# AJH_Wasp_1_0.net
KiCad netlist of a schematic drawn in EAGLE
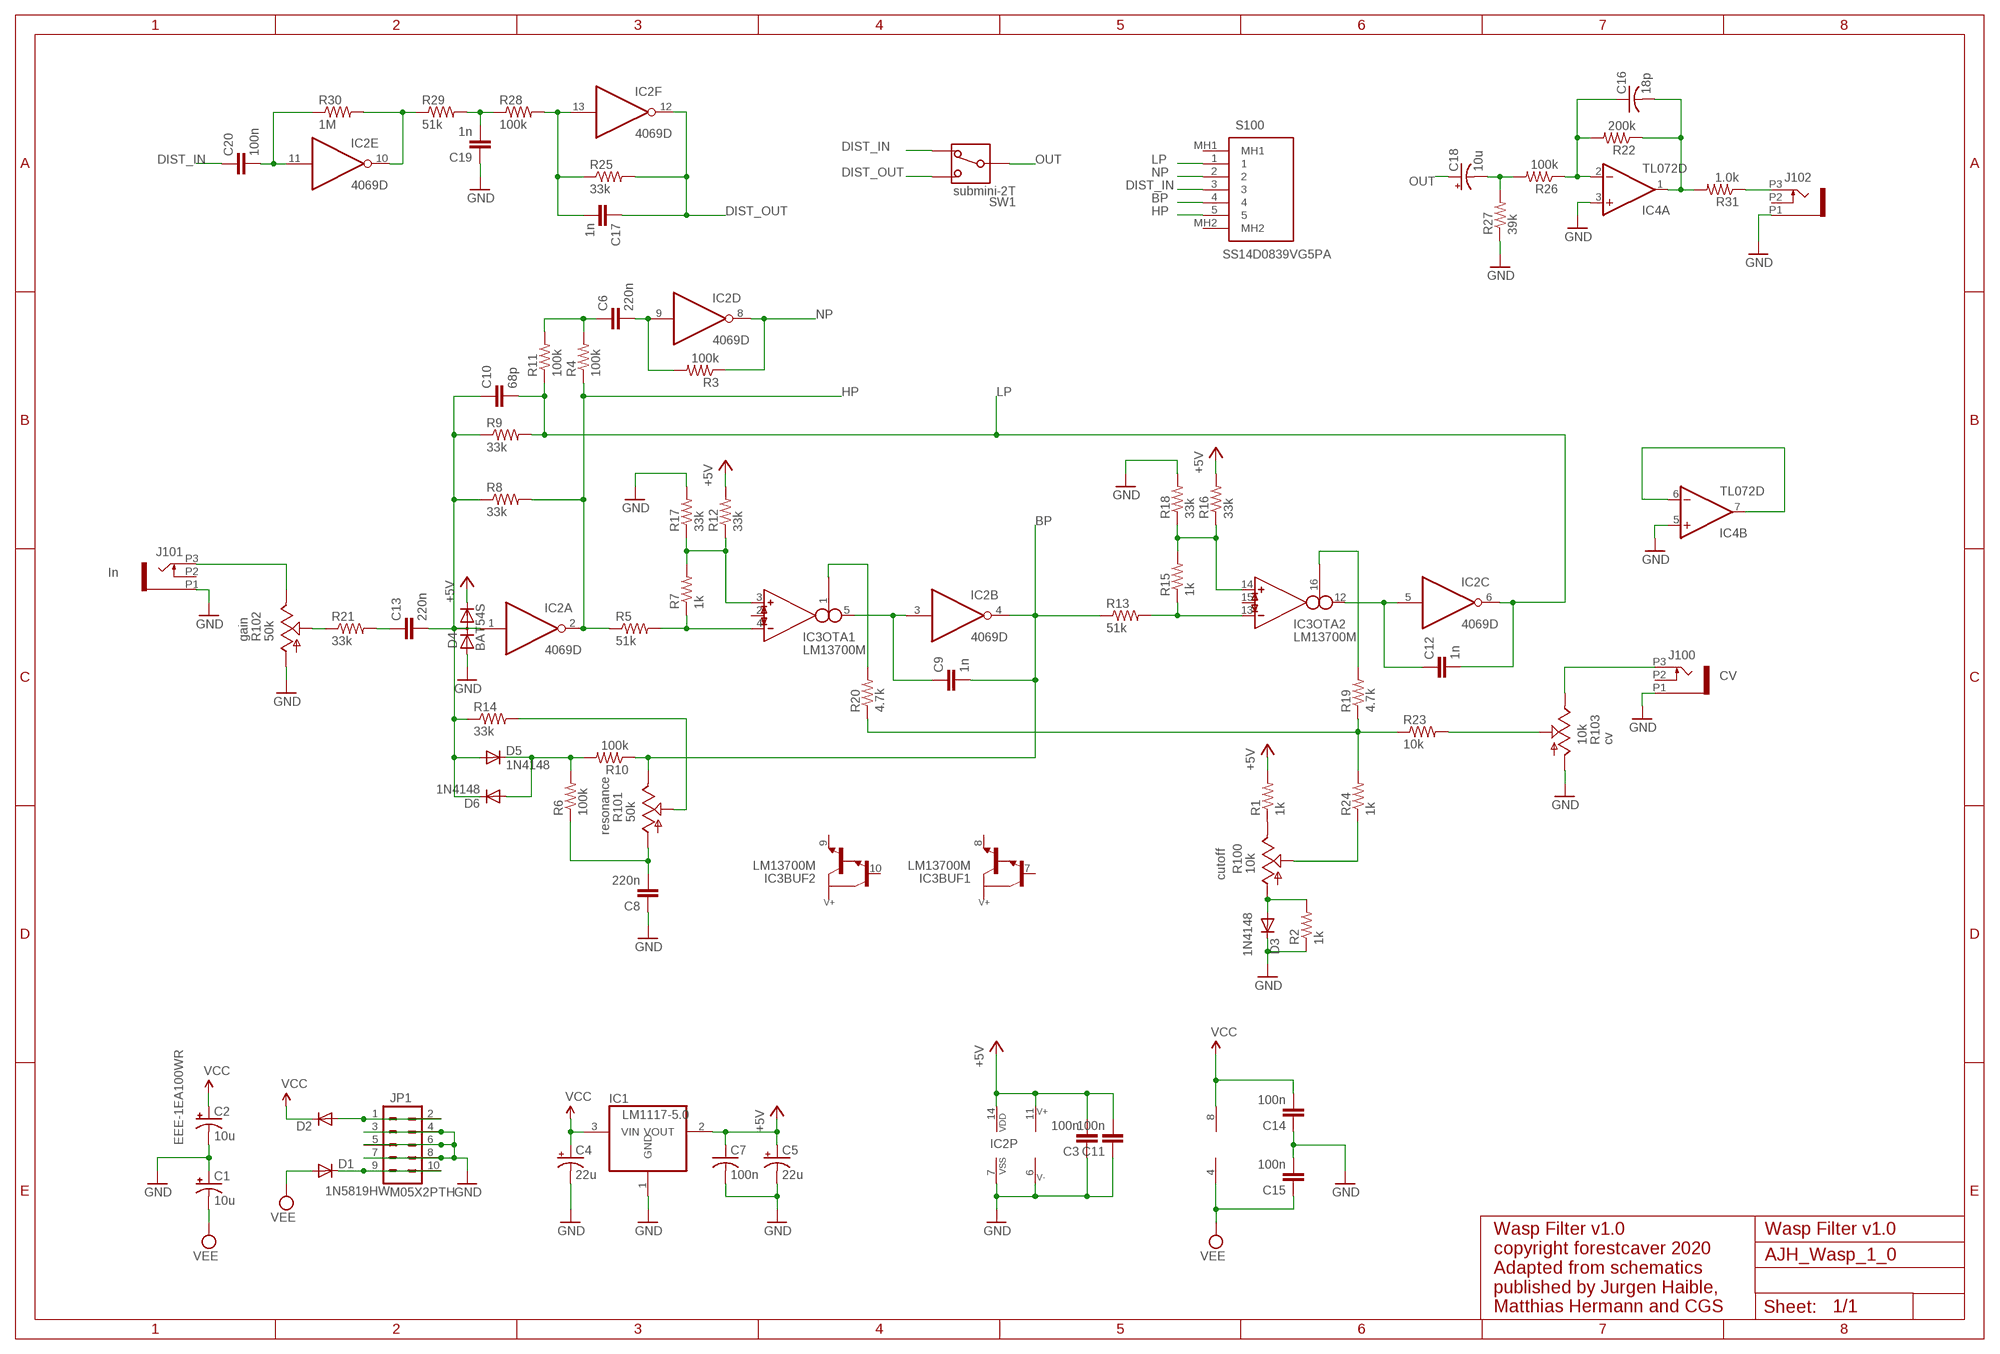
[diagram p0: schematic, sheet 1]

(export (version "E")
  (design (tool "Eeschema 10.0.6"))
  (components
    (comp (ref "C1")
      (value "10u")
      (footprint "eagle-import:PANASONIC_B")
      (libsource (lib "eagle-import") (part "CPOL-USB"))
    )
    (comp (ref "C2")
      (value "10u")
      (footprint "eagle-import:PANASONIC_B")
      (libsource (lib "eagle-import") (part "CPOL-USB"))
    )
    (comp (ref "C3")
      (value "100n")
      (footprint "eagle-import:C0603")
      (libsource (lib "eagle-import") (part "C-EUC0603"))
    )
    (comp (ref "C4")
      (value "22u")
      (footprint "eagle-import:PANASONIC_C")
      (libsource (lib "eagle-import") (part "CPOL-USC"))
    )
    (comp (ref "C5")
      (value "22u")
      (footprint "eagle-import:PANASONIC_C")
      (libsource (lib "eagle-import") (part "CPOL-USC"))
    )
    (comp (ref "C6")
      (value "220n")
      (footprint "eagle-import:C0603")
      (libsource (lib "eagle-import") (part "C-EUC0603"))
    )
    (comp (ref "C7")
      (value "100n")
      (footprint "eagle-import:C0603")
      (libsource (lib "eagle-import") (part "C-USC0603"))
    )
    (comp (ref "C8")
      (value "220n")
      (footprint "eagle-import:C0603")
      (libsource (lib "eagle-import") (part "C-EUC0603"))
    )
    (comp (ref "C9")
      (value "1n")
      (footprint "eagle-import:C0603")
      (libsource (lib "eagle-import") (part "C-EUC0603"))
    )
    (comp (ref "C10")
      (value "68p")
      (footprint "eagle-import:C0603")
      (libsource (lib "eagle-import") (part "C-EUC0603"))
    )
    (comp (ref "C11")
      (value "100n")
      (footprint "eagle-import:C0603")
      (libsource (lib "eagle-import") (part "C-EUC0603"))
    )
    (comp (ref "C12")
      (value "1n")
      (footprint "eagle-import:C0603")
      (libsource (lib "eagle-import") (part "C-EUC0603"))
    )
    (comp (ref "C13")
      (value "220n")
      (footprint "eagle-import:C0603")
      (libsource (lib "eagle-import") (part "C-EUC0603"))
    )
    (comp (ref "C14")
      (value "100n")
      (footprint "eagle-import:C0603")
      (libsource (lib "eagle-import") (part "C-EUC0603"))
    )
    (comp (ref "C15")
      (value "100n")
      (footprint "eagle-import:C0603")
      (libsource (lib "eagle-import") (part "C-EUC0603"))
    )
    (comp (ref "C16")
      (value "18p")
      (footprint "eagle-import:C0603")
      (libsource (lib "eagle-import") (part "C-USC0603"))
    )
    (comp (ref "C17")
      (value "1n")
      (footprint "eagle-import:C0603")
      (libsource (lib "eagle-import") (part "C-EUC0603"))
    )
    (comp (ref "C18")
      (value "10u")
      (footprint "eagle-import:PANASONIC_B")
      (libsource (lib "eagle-import") (part "CPOL-USB"))
    )
    (comp (ref "C19")
      (value "1n")
      (footprint "eagle-import:C0603")
      (libsource (lib "eagle-import") (part "C-EUC0603"))
    )
    (comp (ref "C20")
      (value "100n")
      (footprint "eagle-import:C0603")
      (libsource (lib "eagle-import") (part "C-EUC0603"))
    )
    (comp (ref "D1")
      (value "1N5819HW")
      (footprint "eagle-import:SOD123")
      (libsource (lib "eagle-import") (part "DIODE-SOD123"))
    )
    (comp (ref "D2")
      (value "1N5819HW")
      (footprint "eagle-import:SOD123")
      (libsource (lib "eagle-import") (part "DIODE-SOD123"))
    )
    (comp (ref "D3")
      (value "1N4148")
      (footprint "eagle-import:SOD523")
      (libsource (lib "eagle-import") (part "DIODE-SOD523"))
    )
    (comp (ref "D4")
      (value "BAT54S")
      (footprint "eagle-import:SOT23")
      (libsource (lib "eagle-import") (part "DIODE_2CACA-SOT23"))
    )
    (comp (ref "D5")
      (value "1N4148")
      (footprint "eagle-import:SOD523")
      (libsource (lib "eagle-import") (part "DIODE-SOD523"))
    )
    (comp (ref "D6")
      (value "1N4148")
      (footprint "eagle-import:SOD523")
      (libsource (lib "eagle-import") (part "DIODE-SOD523"))
    )
    (comp (ref "IC1")
      (value "LM1117-5.0")
      (footprint "eagle-import:SOT223")
      (libsource (lib "eagle-import") (part "REG1117"))
    )
    (comp (ref "IC2")
      (value "4069D")
      (footprint "eagle-import:SO14")
      (libsource (lib "eagle-import") (part "4069D"))
    )
    (comp (ref "IC3")
      (value "LM13700M")
      (footprint "eagle-import:SO16")
      (libsource (lib "eagle-import") (part "LM13700M"))
    )
    (comp (ref "IC4")
      (value "TL072D")
      (footprint "eagle-import:SO08")
      (libsource (lib "eagle-import") (part "TL072D"))
    )
    (comp (ref "J100")
      (value "PJ301_THONKICONN8")
      (footprint "eagle-import:WQP_PJ_301M8")
      (fields (field (name "LABEL") "CV"))
      (libsource (lib "eagle-import") (part "PJ301_THONKICONN8"))
    )
    (comp (ref "J101")
      (value "PJ301_THONKICONN8")
      (footprint "eagle-import:WQP_PJ_301M8")
      (fields (field (name "LABEL") "In"))
      (libsource (lib "eagle-import") (part "PJ301_THONKICONN8"))
    )
    (comp (ref "J102")
      (value "PJ301_THONKICONN6")
      (footprint "eagle-import:WQP_PJ_301M6")
      (libsource (lib "eagle-import") (part "PJ301_THONKICONN6"))
    )
    (comp (ref "JP1")
      (value "M05X2PTH")
      (footprint "eagle-import:AVR_ICSP")
      (libsource (lib "eagle-import") (part "M05X2PTH"))
    )
    (comp (ref "R1")
      (value "1k")
      (footprint "eagle-import:R0603")
      (libsource (lib "eagle-import") (part "rcl_334_R-US_R0603"))
    )
    (comp (ref "R2")
      (value "1k")
      (footprint "eagle-import:R0603")
      (libsource (lib "eagle-import") (part "rcl_334_R-US_R0603"))
    )
    (comp (ref "R3")
      (value "100k")
      (footprint "eagle-import:R0603")
      (libsource (lib "eagle-import") (part "rcl_334_R-US_R0603"))
    )
    (comp (ref "R4")
      (value "100k")
      (footprint "eagle-import:R0603")
      (libsource (lib "eagle-import") (part "rcl_334_R-US_R0603"))
    )
    (comp (ref "R5")
      (value "51k")
      (footprint "eagle-import:R0603")
      (libsource (lib "eagle-import") (part "rcl_334_R-US_R0603"))
    )
    (comp (ref "R6")
      (value "100k")
      (footprint "eagle-import:R0603")
      (libsource (lib "eagle-import") (part "rcl_334_R-US_R0603"))
    )
    (comp (ref "R7")
      (value "1k")
      (footprint "eagle-import:R0603")
      (libsource (lib "eagle-import") (part "rcl_334_R-US_R0603"))
    )
    (comp (ref "R8")
      (value "33k")
      (footprint "eagle-import:R0603")
      (libsource (lib "eagle-import") (part "rcl_334_R-US_R0603"))
    )
    (comp (ref "R9")
      (value "33k")
      (footprint "eagle-import:R0603")
      (libsource (lib "eagle-import") (part "rcl_334_R-US_R0603"))
    )
    (comp (ref "R10")
      (value "100k")
      (footprint "eagle-import:R0603")
      (libsource (lib "eagle-import") (part "rcl_334_R-US_R0603"))
    )
    (comp (ref "R11")
      (value "100k")
      (footprint "eagle-import:R0603")
      (libsource (lib "eagle-import") (part "rcl_334_R-US_R0603"))
    )
    (comp (ref "R12")
      (value "33k")
      (footprint "eagle-import:R0603")
      (libsource (lib "eagle-import") (part "rcl_334_R-US_R0603"))
    )
    (comp (ref "R13")
      (value "51k")
      (footprint "eagle-import:R0603")
      (libsource (lib "eagle-import") (part "rcl_334_R-US_R0603"))
    )
    (comp (ref "R14")
      (value "33k")
      (footprint "eagle-import:R0603")
      (libsource (lib "eagle-import") (part "rcl_334_R-US_R0603"))
    )
    (comp (ref "R15")
      (value "1k")
      (footprint "eagle-import:R0603")
      (libsource (lib "eagle-import") (part "rcl_334_R-US_R0603"))
    )
    (comp (ref "R16")
      (value "33k")
      (footprint "eagle-import:R0603")
      (libsource (lib "eagle-import") (part "rcl_334_R-US_R0603"))
    )
    (comp (ref "R17")
      (value "33k")
      (footprint "eagle-import:R0603")
      (libsource (lib "eagle-import") (part "rcl_334_R-US_R0603"))
    )
    (comp (ref "R18")
      (value "33k")
      (footprint "eagle-import:R0603")
      (libsource (lib "eagle-import") (part "rcl_334_R-US_R0603"))
    )
    (comp (ref "R19")
      (value "4.7k")
      (footprint "eagle-import:R0603")
      (libsource (lib "eagle-import") (part "rcl_334_R-US_R0603"))
    )
    (comp (ref "R20")
      (value "4.7k")
      (footprint "eagle-import:R0603")
      (libsource (lib "eagle-import") (part "rcl_334_R-US_R0603"))
    )
    (comp (ref "R21")
      (value "33k")
      (footprint "eagle-import:R0603")
      (libsource (lib "eagle-import") (part "rcl_334_R-US_R0603"))
    )
    (comp (ref "R22")
      (value "200k")
      (footprint "eagle-import:R0603")
      (libsource (lib "eagle-import") (part "R-US_R0603"))
    )
    (comp (ref "R23")
      (value "10k")
      (footprint "eagle-import:R0603")
      (libsource (lib "eagle-import") (part "rcl_334_R-US_R0603"))
    )
    (comp (ref "R24")
      (value "1k")
      (footprint "eagle-import:R0603")
      (libsource (lib "eagle-import") (part "rcl_334_R-US_R0603"))
    )
    (comp (ref "R25")
      (value "33k")
      (footprint "eagle-import:R0603")
      (libsource (lib "eagle-import") (part "rcl_334_R-US_R0603"))
    )
    (comp (ref "R26")
      (value "100k")
      (footprint "eagle-import:R0603")
      (libsource (lib "eagle-import") (part "R-US_R0603"))
    )
    (comp (ref "R27")
      (value "39k")
      (footprint "eagle-import:R0603")
      (libsource (lib "eagle-import") (part "R-US_R0603"))
    )
    (comp (ref "R28")
      (value "100k")
      (footprint "eagle-import:R0603")
      (libsource (lib "eagle-import") (part "rcl_334_R-US_R0603"))
    )
    (comp (ref "R29")
      (value "51k")
      (footprint "eagle-import:R0603")
      (libsource (lib "eagle-import") (part "rcl_334_R-US_R0603"))
    )
    (comp (ref "R30")
      (value "1M")
      (footprint "eagle-import:R0603")
      (libsource (lib "eagle-import") (part "rcl_334_R-US_R0603"))
    )
    (comp (ref "R31")
      (value "1.0k")
      (footprint "eagle-import:R0603")
      (libsource (lib "eagle-import") (part "R-US_R0603"))
    )
    (comp (ref "R100")
      (value "10k")
      (footprint "eagle-import:ALPS_POT_VERTICAL_PS")
      (fields (field (name "LABEL") "cutoff"))
      (libsource (lib "eagle-import") (part "POT_USVERTICAL_PS"))
    )
    (comp (ref "R101")
      (value "50k")
      (footprint "eagle-import:ALPS_POT_VERTICAL_PS")
      (fields (field (name "LABEL") "resonance"))
      (libsource (lib "eagle-import") (part "POT_USVERTICAL_PS"))
    )
    (comp (ref "R102")
      (value "50k")
      (footprint "eagle-import:ALPS_POT_VERTICAL_PS")
      (fields (field (name "LABEL") "gain"))
      (libsource (lib "eagle-import") (part "POT_USVERTICAL_PS"))
    )
    (comp (ref "R103")
      (value "10k")
      (footprint "eagle-import:ALPS_POT_VERTICAL_PS")
      (fields (field (name "LABEL") "cv"))
      (libsource (lib "eagle-import") (part "POT_USVERTICAL_PS"))
    )
    (comp (ref "S100")
      (value "SS14D0839VG5PA")
      (footprint "eagle-import:SS14D0839VG5PA")
      (fields (field (name "MOUSER_PART_NUMBER") "611-SS-14D0839-VG5PA"))
      (libsource (lib "eagle-import") (part "SS14D0839VG5PA"))
    )
    (comp (ref "SW1")
      (value "submini-2T")
      (footprint "eagle-import:SPDT-SUB")
      (libsource (lib "eagle-import") (part "SPDTT"))
    )
  )
  (nets
    (net (code "1") (name "+5V") (class "Default")
      (node (ref "C11") (pin "2") (pinfunction "2_2") (pintype "passive"))
      (node (ref "C3") (pin "2") (pinfunction "2_2") (pintype "passive"))
      (node (ref "C5") (pin "+") (pinfunction "+_+") (pintype "passive"))
      (node (ref "C7") (pin "1") (pinfunction "1_1") (pintype "passive"))
      (node (ref "D4") (pin "2") (pinfunction "C_2") (pintype "passive"))
      (node (ref "IC1") (pin "2") (pinfunction "VOUT_2") (pintype "output"))
      (node (ref "IC2") (pin "14") (pinfunction "VDD_14") (pintype "power_in"))
      (node (ref "IC3") (pin "11") (pinfunction "V+_11") (pintype "power_in"))
      (node (ref "R1") (pin "2") (pinfunction "2_2") (pintype "passive"))
      (node (ref "R12") (pin "2") (pinfunction "2_2") (pintype "passive"))
      (node (ref "R16") (pin "2") (pinfunction "2_2") (pintype "passive"))
    )
    (net (code "2") (name "/BP") (class "Default")
      (node (ref "C9") (pin "2") (pinfunction "2_2") (pintype "passive"))
      (node (ref "IC2") (pin "4") (pinfunction "O_4") (pintype "output"))
      (node (ref "R10") (pin "1") (pinfunction "1_1") (pintype "passive"))
      (node (ref "R101") (pin "P$1") (pinfunction "E_P$1") (pintype "passive"))
      (node (ref "R13") (pin "1") (pinfunction "1_1") (pintype "passive"))
      (node (ref "S100") (pin "4") (pinfunction "4_4") (pintype "bidirectional"))
    )
    (net (code "3") (name "/DIST_IN") (class "Default")
      (node (ref "C20") (pin "1") (pinfunction "1_1") (pintype "passive"))
      (node (ref "S100") (pin "3") (pinfunction "3_3") (pintype "bidirectional"))
      (node (ref "SW1") (pin "P$3") (pinfunction "P$3_P$3") (pintype "passive"))
    )
    (net (code "4") (name "/DIST_OUT") (class "Default")
      (node (ref "C17") (pin "1") (pinfunction "1_1") (pintype "passive"))
      (node (ref "IC2") (pin "12") (pinfunction "O_12") (pintype "output"))
      (node (ref "R25") (pin "2") (pinfunction "2_2") (pintype "passive"))
      (node (ref "SW1") (pin "P$1") (pinfunction "P$1_P$1") (pintype "passive"))
    )
    (net (code "5") (name "/HP") (class "Default")
      (node (ref "IC2") (pin "2") (pinfunction "O_2") (pintype "output"))
      (node (ref "R4") (pin "1") (pinfunction "1_1") (pintype "passive"))
      (node (ref "R5") (pin "1") (pinfunction "1_1") (pintype "passive"))
      (node (ref "R8") (pin "2") (pinfunction "2_2") (pintype "passive"))
      (node (ref "S100") (pin "5") (pinfunction "5_5") (pintype "bidirectional"))
    )
    (net (code "6") (name "/LP") (class "Default")
      (node (ref "C10") (pin "2") (pinfunction "2_2") (pintype "passive"))
      (node (ref "C12") (pin "2") (pinfunction "2_2") (pintype "passive"))
      (node (ref "IC2") (pin "6") (pinfunction "O_6") (pintype "output"))
      (node (ref "R11") (pin "1") (pinfunction "1_1") (pintype "passive"))
      (node (ref "R9") (pin "2") (pinfunction "2_2") (pintype "passive"))
      (node (ref "S100") (pin "1") (pinfunction "1_1") (pintype "bidirectional"))
    )
    (net (code "7") (name "/NP") (class "Default")
      (node (ref "IC2") (pin "8") (pinfunction "O_8") (pintype "output"))
      (node (ref "R3") (pin "1") (pinfunction "1_1") (pintype "passive"))
      (node (ref "S100") (pin "2") (pinfunction "2_2") (pintype "bidirectional"))
    )
    (net (code "8") (name "/OUT") (class "Default")
      (node (ref "C18") (pin "+") (pinfunction "+_+") (pintype "passive"))
      (node (ref "SW1") (pin "P$2") (pinfunction "P$2_P$2") (pintype "passive"))
    )
    (net (code "9") (name "GND") (class "Default")
      (node (ref "C1") (pin "+") (pinfunction "+_+") (pintype "passive"))
      (node (ref "C11") (pin "1") (pinfunction "1_1") (pintype "passive"))
      (node (ref "C14") (pin "1") (pinfunction "1_1") (pintype "passive"))
      (node (ref "C15") (pin "2") (pinfunction "2_2") (pintype "passive"))
      (node (ref "C19") (pin "1") (pinfunction "1_1") (pintype "passive"))
      (node (ref "C2") (pin "-") (pinfunction "-_-") (pintype "passive"))
      (node (ref "C3") (pin "1") (pinfunction "1_1") (pintype "passive"))
      (node (ref "C4") (pin "-") (pinfunction "-_-") (pintype "passive"))
      (node (ref "C5") (pin "-") (pinfunction "-_-") (pintype "passive"))
      (node (ref "C7") (pin "2") (pinfunction "2_2") (pintype "passive"))
      (node (ref "C8") (pin "1") (pinfunction "1_1") (pintype "passive"))
      (node (ref "D3") (pin "C") (pinfunction "C_C") (pintype "passive"))
      (node (ref "D4") (pin "1") (pinfunction "A_1") (pintype "passive"))
      (node (ref "IC1") (pin "1") (pinfunction "GND_1") (pintype "power_in"))
      (node (ref "IC2") (pin "7") (pinfunction "VSS_7") (pintype "power_in"))
      (node (ref "IC3") (pin "6") (pinfunction "V-_6") (pintype "power_in"))
      (node (ref "IC4") (pin "3") (pinfunction "+IN_3") (pintype "input"))
      (node (ref "IC4") (pin "5") (pinfunction "+IN_5") (pintype "input"))
      (node (ref "J100") (pin "P1") (pinfunction "1_P1") (pintype "passive"))
      (node (ref "J101") (pin "P1") (pinfunction "1_P1") (pintype "passive"))
      (node (ref "J102") (pin "P1") (pinfunction "1_P1") (pintype "passive"))
      (node (ref "JP1") (pin "3") (pinfunction "3_3") (pintype "passive"))
      (node (ref "JP1") (pin "4") (pinfunction "4_4") (pintype "passive"))
      (node (ref "JP1") (pin "5") (pinfunction "5_5") (pintype "passive"))
      (node (ref "JP1") (pin "6") (pinfunction "6_6") (pintype "passive"))
      (node (ref "JP1") (pin "7") (pinfunction "7_7") (pintype "passive"))
      (node (ref "JP1") (pin "8") (pinfunction "8_8") (pintype "passive"))
      (node (ref "R102") (pin "P$3") (pinfunction "A_P$3") (pintype "passive"))
      (node (ref "R103") (pin "P$3") (pinfunction "A_P$3") (pintype "passive"))
      (node (ref "R17") (pin "2") (pinfunction "2_2") (pintype "passive"))
      (node (ref "R18") (pin "2") (pinfunction "2_2") (pintype "passive"))
      (node (ref "R2") (pin "1") (pinfunction "1_1") (pintype "passive"))
      (node (ref "R27") (pin "1") (pinfunction "1_1") (pintype "passive"))
    )
    (net (code "10") (name "Net-(C6-Pad1)") (class "Default")
      (node (ref "C6") (pin "1") (pinfunction "1_1") (pintype "passive"))
      (node (ref "R11") (pin "2") (pinfunction "2_2") (pintype "passive"))
      (node (ref "R4") (pin "2") (pinfunction "2_2") (pintype "passive"))
    )
    (net (code "11") (name "Net-(C13-Pad1)") (class "Default")
      (node (ref "C13") (pin "1") (pinfunction "1_1") (pintype "passive"))
      (node (ref "R21") (pin "2") (pinfunction "2_2") (pintype "passive"))
    )
    (net (code "12") (name "Net-(C18-Pad-)") (class "Default")
      (node (ref "C18") (pin "-") (pinfunction "-_-") (pintype "passive"))
      (node (ref "R26") (pin "2") (pinfunction "2_2") (pintype "passive"))
      (node (ref "R27") (pin "2") (pinfunction "2_2") (pintype "passive"))
    )
    (net (code "13") (name "Net-(C19-Pad2)") (class "Default")
      (node (ref "C19") (pin "2") (pinfunction "2_2") (pintype "passive"))
      (node (ref "R28") (pin "1") (pinfunction "1_1") (pintype "passive"))
      (node (ref "R29") (pin "2") (pinfunction "2_2") (pintype "passive"))
    )
    (net (code "14") (name "Net-(D1-PadC)") (class "Default")
      (node (ref "D1") (pin "C") (pinfunction "C_C") (pintype "passive"))
      (node (ref "JP1") (pin "10") (pinfunction "10_10") (pintype "passive"))
      (node (ref "JP1") (pin "9") (pinfunction "9_9") (pintype "passive"))
    )
    (net (code "15") (name "Net-(D2-PadA)") (class "Default")
      (node (ref "D2") (pin "A") (pinfunction "A_A") (pintype "passive"))
      (node (ref "JP1") (pin "1") (pinfunction "1_1") (pintype "passive"))
      (node (ref "JP1") (pin "2") (pinfunction "2_2") (pintype "passive"))
    )
    (net (code "16") (name "Net-(D4-AC)") (class "Default")
      (node (ref "C10") (pin "1") (pinfunction "1_1") (pintype "passive"))
      (node (ref "C13") (pin "2") (pinfunction "2_2") (pintype "passive"))
      (node (ref "D4") (pin "3") (pinfunction "AC_3") (pintype "passive"))
      (node (ref "D5") (pin "A") (pinfunction "A_A") (pintype "passive"))
      (node (ref "D6") (pin "C") (pinfunction "C_C") (pintype "passive"))
      (node (ref "IC2") (pin "1") (pinfunction "I_1") (pintype "input"))
      (node (ref "R14") (pin "1") (pinfunction "1_1") (pintype "passive"))
      (node (ref "R8") (pin "1") (pinfunction "1_1") (pintype "passive"))
      (node (ref "R9") (pin "1") (pinfunction "1_1") (pintype "passive"))
    )
    (net (code "17") (name "Net-(D5-PadC)") (class "Default")
      (node (ref "D5") (pin "C") (pinfunction "C_C") (pintype "passive"))
      (node (ref "D6") (pin "A") (pinfunction "A_A") (pintype "passive"))
      (node (ref "R10") (pin "2") (pinfunction "2_2") (pintype "passive"))
      (node (ref "R6") (pin "2") (pinfunction "2_2") (pintype "passive"))
    )
    (net (code "18") (name "Net-(IC2B-I)") (class "Default")
      (node (ref "C9") (pin "1") (pinfunction "1_1") (pintype "passive"))
      (node (ref "IC2") (pin "3") (pinfunction "I_3") (pintype "input"))
      (node (ref "IC3") (pin "5") (pinfunction "OUT_5") (pintype "output"))
    )
    (net (code "19") (name "Net-(IC2C-I)") (class "Default")
      (node (ref "C12") (pin "1") (pinfunction "1_1") (pintype "passive"))
      (node (ref "IC2") (pin "5") (pinfunction "I_5") (pintype "input"))
      (node (ref "IC3") (pin "12") (pinfunction "OUT_12") (pintype "output"))
    )
    (net (code "20") (name "Net-(IC2D-I)") (class "Default")
      (node (ref "C6") (pin "2") (pinfunction "2_2") (pintype "passive"))
      (node (ref "IC2") (pin "9") (pinfunction "I_9") (pintype "input"))
      (node (ref "R3") (pin "2") (pinfunction "2_2") (pintype "passive"))
    )
    (net (code "21") (name "Net-(IC2E-I)") (class "Default")
      (node (ref "C20") (pin "2") (pinfunction "2_2") (pintype "passive"))
      (node (ref "IC2") (pin "11") (pinfunction "I_11") (pintype "input"))
      (node (ref "R30") (pin "1") (pinfunction "1_1") (pintype "passive"))
    )
    (net (code "22") (name "Net-(IC2E-O)") (class "Default")
      (node (ref "IC2") (pin "10") (pinfunction "O_10") (pintype "output"))
      (node (ref "R29") (pin "1") (pinfunction "1_1") (pintype "passive"))
      (node (ref "R30") (pin "2") (pinfunction "2_2") (pintype "passive"))
    )
    (net (code "23") (name "Net-(IC2F-I)") (class "Default")
      (node (ref "C17") (pin "2") (pinfunction "2_2") (pintype "passive"))
      (node (ref "IC2") (pin "13") (pinfunction "I_13") (pintype "input"))
      (node (ref "R25") (pin "1") (pinfunction "1_1") (pintype "passive"))
      (node (ref "R28") (pin "2") (pinfunction "2_2") (pintype "passive"))
    )
    (net (code "24") (name "Net-(IC3C-IN_N)") (class "Default")
      (node (ref "IC3") (pin "4") (pinfunction "IN_N_4") (pintype "input"))
      (node (ref "R5") (pin "2") (pinfunction "2_2") (pintype "passive"))
      (node (ref "R7") (pin "1") (pinfunction "1_1") (pintype "passive"))
    )
    (net (code "25") (name "Net-(IC3C-IN_P)") (class "Default")
      (node (ref "IC3") (pin "3") (pinfunction "IN_P_3") (pintype "input"))
      (node (ref "R12") (pin "1") (pinfunction "1_1") (pintype "passive"))
      (node (ref "R17") (pin "1") (pinfunction "1_1") (pintype "passive"))
      (node (ref "R7") (pin "2") (pinfunction "2_2") (pintype "passive"))
    )
    (net (code "26") (name "Net-(IC3C-I_BIAS)") (class "Default")
      (node (ref "IC3") (pin "1") (pinfunction "I_BIAS_1") (pintype "input"))
      (node (ref "R20") (pin "2") (pinfunction "2_2") (pintype "passive"))
    )
    (net (code "27") (name "Net-(IC3D-IN_N)") (class "Default")
      (node (ref "IC3") (pin "13") (pinfunction "IN_N_13") (pintype "input"))
      (node (ref "R13") (pin "2") (pinfunction "2_2") (pintype "passive"))
      (node (ref "R15") (pin "1") (pinfunction "1_1") (pintype "passive"))
    )
    (net (code "28") (name "Net-(IC3D-IN_P)") (class "Default")
      (node (ref "IC3") (pin "14") (pinfunction "IN_P_14") (pintype "input"))
      (node (ref "R15") (pin "2") (pinfunction "2_2") (pintype "passive"))
      (node (ref "R16") (pin "1") (pinfunction "1_1") (pintype "passive"))
      (node (ref "R18") (pin "1") (pinfunction "1_1") (pintype "passive"))
    )
    (net (code "29") (name "Net-(IC3D-I_BIAS)") (class "Default")
      (node (ref "IC3") (pin "16") (pinfunction "I_BIAS_16") (pintype "input"))
      (node (ref "R19") (pin "2") (pinfunction "2_2") (pintype "passive"))
    )
    (net (code "30") (name "Net-(IC4A--IN)") (class "Default")
      (node (ref "C16") (pin "1") (pinfunction "1_1") (pintype "passive"))
      (node (ref "IC4") (pin "2") (pinfunction "-IN_2") (pintype "input"))
      (node (ref "R22") (pin "2") (pinfunction "2_2") (pintype "passive"))
      (node (ref "R26") (pin "1") (pinfunction "1_1") (pintype "passive"))
    )
    (net (code "31") (name "Net-(IC4A-OUT)") (class "Default")
      (node (ref "C16") (pin "2") (pinfunction "2_2") (pintype "passive"))
      (node (ref "IC4") (pin "1") (pinfunction "OUT_1") (pintype "output"))
      (node (ref "R22") (pin "1") (pinfunction "1_1") (pintype "passive"))
      (node (ref "R31") (pin "2") (pinfunction "2_2") (pintype "passive"))
    )
    (net (code "32") (name "Net-(IC4B--IN)") (class "Default")
      (node (ref "IC4") (pin "6") (pinfunction "-IN_6") (pintype "input"))
      (node (ref "IC4") (pin "7") (pinfunction "OUT_7") (pintype "output"))
    )
    (net (code "33") (name "Net-(J100-3)") (class "Default")
      (node (ref "J100") (pin "P3") (pinfunction "3_P3") (pintype "passive"))
      (node (ref "R103") (pin "P$1") (pinfunction "E_P$1") (pintype "passive"))
    )
    (net (code "34") (name "Net-(J101-3)") (class "Default")
      (node (ref "J101") (pin "P3") (pinfunction "3_P3") (pintype "passive"))
      (node (ref "R102") (pin "P$1") (pinfunction "E_P$1") (pintype "passive"))
    )
    (net (code "35") (name "Net-(J102-3)") (class "Default")
      (node (ref "J102") (pin "P3") (pinfunction "3_P3") (pintype "passive"))
      (node (ref "R31") (pin "1") (pinfunction "1_1") (pintype "passive"))
    )
    (net (code "36") (name "Net-(R19-Pad1)") (class "Default")
      (node (ref "R19") (pin "1") (pinfunction "1_1") (pintype "passive"))
      (node (ref "R20") (pin "1") (pinfunction "1_1") (pintype "passive"))
      (node (ref "R23") (pin "1") (pinfunction "1_1") (pintype "passive"))
      (node (ref "R24") (pin "2") (pinfunction "2_2") (pintype "passive"))
    )
    (net (code "37") (name "Net-(R100-A)") (class "Default")
      (node (ref "D3") (pin "A") (pinfunction "A_A") (pintype "passive"))
      (node (ref "R100") (pin "P$3") (pinfunction "A_P$3") (pintype "passive"))
      (node (ref "R2") (pin "2") (pinfunction "2_2") (pintype "passive"))
    )
    (net (code "38") (name "Net-(R100-E)") (class "Default")
      (node (ref "R1") (pin "1") (pinfunction "1_1") (pintype "passive"))
      (node (ref "R100") (pin "P$1") (pinfunction "E_P$1") (pintype "passive"))
    )
    (net (code "39") (name "Net-(R100-S)") (class "Default")
      (node (ref "R100") (pin "P$2") (pinfunction "S_P$2") (pintype "passive"))
      (node (ref "R24") (pin "1") (pinfunction "1_1") (pintype "passive"))
    )
    (net (code "40") (name "Net-(R101-A)") (class "Default")
      (node (ref "C8") (pin "2") (pinfunction "2_2") (pintype "passive"))
      (node (ref "R101") (pin "P$3") (pinfunction "A_P$3") (pintype "passive"))
      (node (ref "R6") (pin "1") (pinfunction "1_1") (pintype "passive"))
    )
    (net (code "41") (name "Net-(R101-S)") (class "Default")
      (node (ref "R101") (pin "P$2") (pinfunction "S_P$2") (pintype "passive"))
      (node (ref "R14") (pin "2") (pinfunction "2_2") (pintype "passive"))
    )
    (net (code "42") (name "Net-(R102-S)") (class "Default")
      (node (ref "R102") (pin "P$2") (pinfunction "S_P$2") (pintype "passive"))
      (node (ref "R21") (pin "1") (pinfunction "1_1") (pintype "passive"))
    )
    (net (code "43") (name "Net-(R103-S)") (class "Default")
      (node (ref "R103") (pin "P$2") (pinfunction "S_P$2") (pintype "passive"))
      (node (ref "R23") (pin "2") (pinfunction "2_2") (pintype "passive"))
    )
    (net (code "44") (name "VCC") (class "Default")
      (node (ref "C14") (pin "2") (pinfunction "2_2") (pintype "passive"))
      (node (ref "C2") (pin "+") (pinfunction "+_+") (pintype "passive"))
      (node (ref "C4") (pin "+") (pinfunction "+_+") (pintype "passive"))
      (node (ref "D2") (pin "C") (pinfunction "C_C") (pintype "passive"))
      (node (ref "IC1") (pin "3") (pinfunction "VIN_3") (pintype "input"))
      (node (ref "IC4") (pin "8") (pinfunction "V+_8") (pintype "power_in"))
    )
    (net (code "45") (name "VEE") (class "Default")
      (node (ref "C1") (pin "-") (pinfunction "-_-") (pintype "passive"))
      (node (ref "C15") (pin "1") (pinfunction "1_1") (pintype "passive"))
      (node (ref "D1") (pin "A") (pinfunction "A_A") (pintype "passive"))
      (node (ref "IC4") (pin "4") (pinfunction "V-_4") (pintype "power_in"))
    )
    (net (code "46") (name "unconnected-(IC3A-B-Pad7)") (class "Default")
      (node (ref "IC3") (pin "7") (pinfunction "B_7") (pintype "passive"))
    )
    (net (code "47") (name "unconnected-(IC3A-E-Pad8)") (class "Default")
      (node (ref "IC3") (pin "8") (pinfunction "E_8") (pintype "passive"))
    )
    (net (code "48") (name "unconnected-(IC3B-B-Pad10)") (class "Default")
      (node (ref "IC3") (pin "10") (pinfunction "B_10") (pintype "passive"))
    )
    (net (code "49") (name "unconnected-(IC3B-E-Pad9)") (class "Default")
      (node (ref "IC3") (pin "9") (pinfunction "E_9") (pintype "passive"))
    )
    (net (code "50") (name "unconnected-(IC3C-I_DIODE-Pad2)") (class "Default")
      (node (ref "IC3") (pin "2") (pinfunction "I_DIODE_2") (pintype "input"))
    )
    (net (code "51") (name "unconnected-(IC3D-I_DIODE-Pad15)") (class "Default")
      (node (ref "IC3") (pin "15") (pinfunction "I_DIODE_15") (pintype "input"))
    )
    (net (code "52") (name "unconnected-(J100-2-PadP2)") (class "Default")
      (node (ref "J100") (pin "P2") (pinfunction "2_P2") (pintype "passive"))
    )
    (net (code "53") (name "unconnected-(J101-2-PadP2)") (class "Default")
      (node (ref "J101") (pin "P2") (pinfunction "2_P2") (pintype "passive"))
    )
    (net (code "54") (name "unconnected-(J102-2-PadP2)") (class "Default")
      (node (ref "J102") (pin "P2") (pinfunction "2_P2") (pintype "passive"))
    )
    (net (code "55") (name "unconnected-(S100-PadMH1)") (class "Default")
      (node (ref "S100") (pin "MH1") (pinfunction "MH1_MH1") (pintype "bidirectional"))
    )
    (net (code "56") (name "unconnected-(S100-PadMH2)") (class "Default")
      (node (ref "S100") (pin "MH2") (pinfunction "MH2_MH2") (pintype "bidirectional"))
    )
  )
)
